# PCB.net
KiCad netlist of a schematic drawn in EAGLE
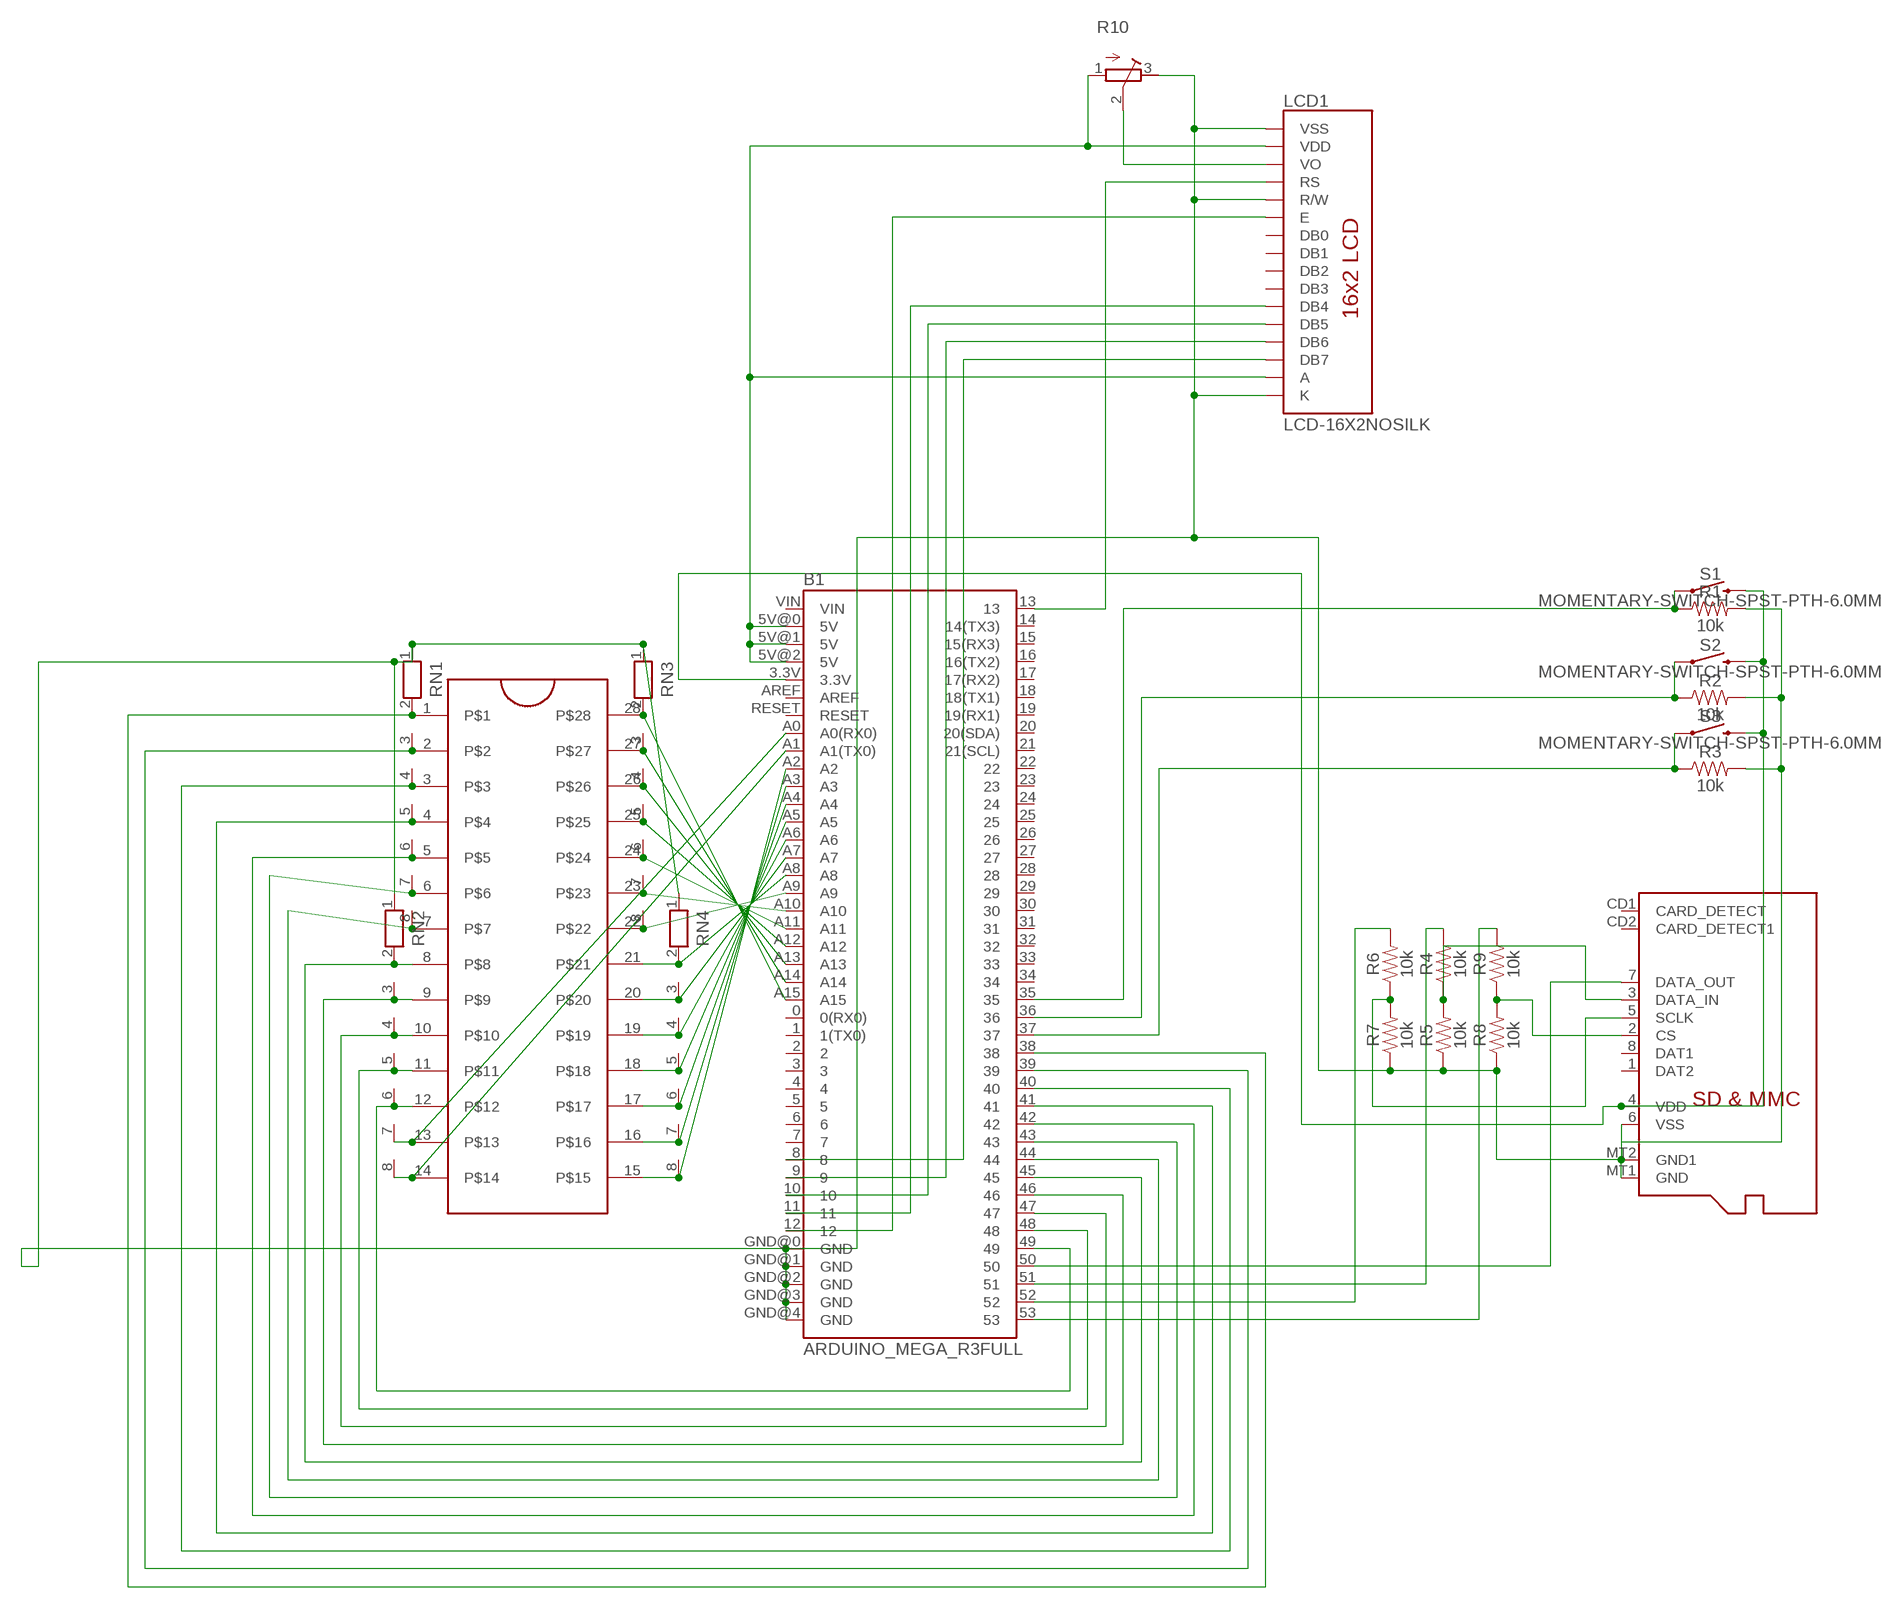
[diagram p0: schematic, sheet 1]

(export (version "E")
  (design (tool "Eeschema 10.0.6"))
  (components
    (comp (ref "B1")
      (value "ARDUINO_MEGA_R3FULL")
      (footprint "eagle-import:ARDUINO_MEGA")
      (libsource (lib "eagle-import") (part "ARDUINO_MEGA_R3FULL"))
    )
    (comp (ref "LCD1")
      (value "LCD-16X2NOSILK")
      (footprint "eagle-import:LCD-16X2_NOSILK")
      (libsource (lib "eagle-import") (part "LCD-16X2NOSILK"))
    )
    (comp (ref "R1")
      (value "10k")
      (footprint "eagle-import:AXIAL-0.3")
      (libsource (lib "eagle-import") (part "10KOHM-HORIZ-1/4W-5%"))
    )
    (comp (ref "R2")
      (value "10k")
      (footprint "eagle-import:AXIAL-0.3")
      (libsource (lib "eagle-import") (part "10KOHM-HORIZ-1/4W-5%"))
    )
    (comp (ref "R3")
      (value "10k")
      (footprint "eagle-import:AXIAL-0.3")
      (libsource (lib "eagle-import") (part "10KOHM-HORIZ-1/4W-5%"))
    )
    (comp (ref "R4")
      (value "10k")
      (footprint "eagle-import:AXIAL-0.3")
      (libsource (lib "eagle-import") (part "10KOHM-HORIZ-1/4W-5%"))
    )
    (comp (ref "R5")
      (value "10k")
      (footprint "eagle-import:AXIAL-0.3")
      (libsource (lib "eagle-import") (part "10KOHM-HORIZ-1/4W-5%"))
    )
    (comp (ref "R6")
      (value "10k")
      (footprint "eagle-import:AXIAL-0.3")
      (libsource (lib "eagle-import") (part "10KOHM-HORIZ-1/4W-5%"))
    )
    (comp (ref "R7")
      (value "10k")
      (footprint "eagle-import:AXIAL-0.3")
      (libsource (lib "eagle-import") (part "10KOHM-HORIZ-1/4W-5%"))
    )
    (comp (ref "R8")
      (value "10k")
      (footprint "eagle-import:AXIAL-0.3")
      (libsource (lib "eagle-import") (part "10KOHM-HORIZ-1/4W-5%"))
    )
    (comp (ref "R9")
      (value "10k")
      (footprint "eagle-import:AXIAL-0.3")
      (libsource (lib "eagle-import") (part "10KOHM-HORIZ-1/4W-5%"))
    )
    (comp (ref "R10")
      (value "R-TRIMM3339P")
      (footprint "eagle-import:RTRIM3339P")
      (libsource (lib "eagle-import") (part "R-TRIMM3339P"))
    )
    (comp (ref "RN1")
      (value "RN07")
      (footprint "eagle-import:RN-8")
      (libsource (lib "eagle-import") (part "RN07"))
    )
    (comp (ref "RN2")
      (value "RN07")
      (footprint "eagle-import:RN-8")
      (libsource (lib "eagle-import") (part "RN07"))
    )
    (comp (ref "RN3")
      (value "RN07")
      (footprint "eagle-import:RN-8")
      (libsource (lib "eagle-import") (part "RN07"))
    )
    (comp (ref "RN4")
      (value "RN07")
      (footprint "eagle-import:RN-8")
      (libsource (lib "eagle-import") (part "RN07"))
    )
    (comp (ref "S1")
      (value "MOMENTARY-SWITCH-SPST-PTH-6.0MM")
      (footprint "eagle-import:TACTILE_SWITCH_PTH_6.0MM")
      (libsource (lib "eagle-import") (part "MOMENTARY-SWITCH-SPST-PTH-6.0MM"))
    )
    (comp (ref "S2")
      (value "MOMENTARY-SWITCH-SPST-PTH-6.0MM")
      (footprint "eagle-import:TACTILE_SWITCH_PTH_6.0MM")
      (libsource (lib "eagle-import") (part "MOMENTARY-SWITCH-SPST-PTH-6.0MM"))
    )
    (comp (ref "S3")
      (value "MOMENTARY-SWITCH-SPST-PTH-6.0MM")
      (footprint "eagle-import:TACTILE_SWITCH_PTH_6.0MM")
      (libsource (lib "eagle-import") (part "MOMENTARY-SWITCH-SPST-PTH-6.0MM"))
    )
    (comp (ref "U$1")
      (value "MICROSD")
      (footprint "eagle-import:MICROSD")
      (libsource (lib "eagle-import") (part "MICROSD"))
    )
    (comp (ref "U$2")
      (value "ZIFSOCKET-28-3ZIFFSOCKET-28-3")
      (footprint "eagle-import:DIL28-3-ZIF_SOCKET")
      (libsource (lib "eagle-import") (part "ZIFSOCKET-28-3ZIFFSOCKET-28-3"))
    )
  )
  (nets
    (net (code "1") (name "Net-(B1-A0(RX0))") (class "Default")
      (node (ref "B1") (pin "A0") (pinfunction "A0(RX0)_A0") (pintype "bidirectional"))
      (node (ref "RN2") (pin "7") (pinfunction "7_7") (pintype "passive"))
      (node (ref "U$2") (pin "13") (pinfunction "P$13_13") (pintype "bidirectional"))
    )
    (net (code "2") (name "Net-(B1-A1(TX0))") (class "Default")
      (node (ref "B1") (pin "A1") (pinfunction "A1(TX0)_A1") (pintype "bidirectional"))
      (node (ref "RN2") (pin "8") (pinfunction "8_8") (pintype "passive"))
      (node (ref "U$2") (pin "14") (pinfunction "P$14_14") (pintype "bidirectional"))
    )
    (net (code "3") (name "Net-(LCD1-A)") (class "Default")
      (node (ref "B1") (pin "5V@0") (pinfunction "5V_5V@0") (pintype "bidirectional"))
      (node (ref "B1") (pin "5V@1") (pinfunction "5V_5V@1") (pintype "bidirectional"))
      (node (ref "B1") (pin "5V@2") (pinfunction "5V_5V@2") (pintype "bidirectional"))
      (node (ref "LCD1") (pin "15") (pinfunction "A_15") (pintype "power_in"))
      (node (ref "LCD1") (pin "2") (pinfunction "VDD_2") (pintype "power_in"))
      (node (ref "R10") (pin "1") (pinfunction "A_1") (pintype "passive"))
    )
    (net (code "4") (name "Net-(LCD1-DB4)") (class "Default")
      (node (ref "B1") (pin "11") (pinfunction "11_11") (pintype "bidirectional"))
      (node (ref "LCD1") (pin "11") (pinfunction "DB4_11") (pintype "bidirectional"))
    )
    (net (code "5") (name "Net-(LCD1-DB5)") (class "Default")
      (node (ref "B1") (pin "10") (pinfunction "10_10") (pintype "bidirectional"))
      (node (ref "LCD1") (pin "12") (pinfunction "DB5_12") (pintype "bidirectional"))
    )
    (net (code "6") (name "Net-(LCD1-DB6)") (class "Default")
      (node (ref "B1") (pin "9") (pinfunction "9_9") (pintype "bidirectional"))
      (node (ref "LCD1") (pin "13") (pinfunction "DB6_13") (pintype "bidirectional"))
    )
    (net (code "7") (name "Net-(LCD1-DB7)") (class "Default")
      (node (ref "B1") (pin "8") (pinfunction "8_8") (pintype "bidirectional"))
      (node (ref "LCD1") (pin "14") (pinfunction "DB7_14") (pintype "bidirectional"))
    )
    (net (code "8") (name "Net-(LCD1-E)") (class "Default")
      (node (ref "B1") (pin "12") (pinfunction "12_12") (pintype "bidirectional"))
      (node (ref "LCD1") (pin "6") (pinfunction "E_6") (pintype "input"))
    )
    (net (code "9") (name "Net-(LCD1-K)") (class "Default")
      (node (ref "B1") (pin "GND@0") (pinfunction "GND_GND@0") (pintype "bidirectional"))
      (node (ref "B1") (pin "GND@1") (pinfunction "GND_GND@1") (pintype "bidirectional"))
      (node (ref "B1") (pin "GND@2") (pinfunction "GND_GND@2") (pintype "bidirectional"))
      (node (ref "B1") (pin "GND@3") (pinfunction "GND_GND@3") (pintype "bidirectional"))
      (node (ref "B1") (pin "GND@4") (pinfunction "GND_GND@4") (pintype "bidirectional"))
      (node (ref "LCD1") (pin "1") (pinfunction "VSS_1") (pintype "power_in"))
      (node (ref "LCD1") (pin "16") (pinfunction "K_16") (pintype "power_in"))
      (node (ref "LCD1") (pin "5") (pinfunction "R/W_5") (pintype "input"))
      (node (ref "R1") (pin "P$2") (pinfunction "2_P$2") (pintype "passive"))
      (node (ref "R10") (pin "3") (pinfunction "E_3") (pintype "passive"))
      (node (ref "R2") (pin "P$2") (pinfunction "2_P$2") (pintype "passive"))
      (node (ref "R3") (pin "P$2") (pinfunction "2_P$2") (pintype "passive"))
      (node (ref "R5") (pin "P$1") (pinfunction "1_P$1") (pintype "passive"))
      (node (ref "R7") (pin "P$1") (pinfunction "1_P$1") (pintype "passive"))
      (node (ref "R8") (pin "P$1") (pinfunction "1_P$1") (pintype "passive"))
      (node (ref "RN1") (pin "1") (pinfunction "1_1") (pintype "passive"))
      (node (ref "RN2") (pin "1") (pinfunction "1_1") (pintype "passive"))
      (node (ref "RN3") (pin "1") (pinfunction "1_1") (pintype "passive"))
      (node (ref "RN4") (pin "1") (pinfunction "1_1") (pintype "passive"))
      (node (ref "U$1") (pin "6") (pinfunction "VSS_6") (pintype "power_in"))
      (node (ref "U$1") (pin "MT1") (pinfunction "GND_MT1") (pintype "power_in"))
      (node (ref "U$1") (pin "MT2") (pinfunction "GND1_MT2") (pintype "power_in"))
    )
    (net (code "10") (name "Net-(LCD1-RS)") (class "Default")
      (node (ref "B1") (pin "13") (pinfunction "13_13") (pintype "bidirectional"))
      (node (ref "LCD1") (pin "4") (pinfunction "RS_4") (pintype "input"))
    )
    (net (code "11") (name "Net-(LCD1-VO)") (class "Default")
      (node (ref "LCD1") (pin "3") (pinfunction "VO_3") (pintype "bidirectional"))
      (node (ref "R10") (pin "2") (pinfunction "S_2") (pintype "passive"))
    )
    (net (code "12") (name "Net-(R1-1)") (class "Default")
      (node (ref "B1") (pin "35") (pinfunction "35_35") (pintype "bidirectional"))
      (node (ref "R1") (pin "P$1") (pinfunction "1_P$1") (pintype "passive"))
      (node (ref "S1") (pin "1") (pinfunction "1_1") (pintype "passive"))
    )
    (net (code "13") (name "Net-(R2-1)") (class "Default")
      (node (ref "B1") (pin "36") (pinfunction "36_36") (pintype "bidirectional"))
      (node (ref "R2") (pin "P$1") (pinfunction "1_P$1") (pintype "passive"))
      (node (ref "S2") (pin "1") (pinfunction "1_1") (pintype "passive"))
    )
    (net (code "14") (name "Net-(R3-1)") (class "Default")
      (node (ref "B1") (pin "37") (pinfunction "37_37") (pintype "bidirectional"))
      (node (ref "R3") (pin "P$1") (pinfunction "1_P$1") (pintype "passive"))
      (node (ref "S3") (pin "1") (pinfunction "1_1") (pintype "passive"))
    )
    (net (code "15") (name "Net-(R4-1)") (class "Default")
      (node (ref "R4") (pin "P$1") (pinfunction "1_P$1") (pintype "passive"))
      (node (ref "R5") (pin "P$2") (pinfunction "2_P$2") (pintype "passive"))
      (node (ref "U$1") (pin "3") (pinfunction "DATA_IN_3") (pintype "input"))
    )
    (net (code "16") (name "Net-(R4-2)") (class "Default")
      (node (ref "B1") (pin "51") (pinfunction "51_51") (pintype "bidirectional"))
      (node (ref "R4") (pin "P$2") (pinfunction "2_P$2") (pintype "passive"))
    )
    (net (code "17") (name "Net-(R6-1)") (class "Default")
      (node (ref "R6") (pin "P$1") (pinfunction "1_P$1") (pintype "passive"))
      (node (ref "R7") (pin "P$2") (pinfunction "2_P$2") (pintype "passive"))
      (node (ref "U$1") (pin "5") (pinfunction "SCLK_5") (pintype "input"))
    )
    (net (code "18") (name "Net-(R6-2)") (class "Default")
      (node (ref "B1") (pin "52") (pinfunction "52_52") (pintype "bidirectional"))
      (node (ref "R6") (pin "P$2") (pinfunction "2_P$2") (pintype "passive"))
    )
    (net (code "19") (name "Net-(R8-2)") (class "Default")
      (node (ref "R8") (pin "P$2") (pinfunction "2_P$2") (pintype "passive"))
      (node (ref "R9") (pin "P$1") (pinfunction "1_P$1") (pintype "passive"))
      (node (ref "U$1") (pin "2") (pinfunction "CS_2") (pintype "input"))
    )
    (net (code "20") (name "Net-(R9-2)") (class "Default")
      (node (ref "B1") (pin "53") (pinfunction "53_53") (pintype "bidirectional"))
      (node (ref "R9") (pin "P$2") (pinfunction "2_P$2") (pintype "passive"))
    )
    (net (code "21") (name "Net-(S1-2)") (class "Default")
      (node (ref "B1") (pin "3.3V") (pinfunction "3.3V_3.3V") (pintype "bidirectional"))
      (node (ref "S1") (pin "3") (pinfunction "2_3") (pintype "passive"))
      (node (ref "S2") (pin "3") (pinfunction "2_3") (pintype "passive"))
      (node (ref "S3") (pin "3") (pinfunction "2_3") (pintype "passive"))
      (node (ref "U$1") (pin "4") (pinfunction "VDD_4") (pintype "power_in"))
    )
    (net (code "22") (name "Net-(U$1-DATA_OUT)") (class "Default")
      (node (ref "B1") (pin "50") (pinfunction "50_50") (pintype "bidirectional"))
      (node (ref "U$1") (pin "7") (pinfunction "DATA_OUT_7") (pintype "output"))
    )
    (net (code "23") (name "Net-(U$2-P$1)") (class "Default")
      (node (ref "B1") (pin "38") (pinfunction "38_38") (pintype "bidirectional"))
      (node (ref "RN1") (pin "2") (pinfunction "2_2") (pintype "passive"))
      (node (ref "U$2") (pin "1") (pinfunction "P$1_1") (pintype "bidirectional"))
    )
    (net (code "24") (name "Net-(U$2-P$2)") (class "Default")
      (node (ref "B1") (pin "39") (pinfunction "39_39") (pintype "bidirectional"))
      (node (ref "RN1") (pin "3") (pinfunction "3_3") (pintype "passive"))
      (node (ref "U$2") (pin "2") (pinfunction "P$2_2") (pintype "bidirectional"))
    )
    (net (code "25") (name "Net-(U$2-P$3)") (class "Default")
      (node (ref "B1") (pin "40") (pinfunction "40_40") (pintype "bidirectional"))
      (node (ref "RN1") (pin "4") (pinfunction "4_4") (pintype "passive"))
      (node (ref "U$2") (pin "3") (pinfunction "P$3_3") (pintype "bidirectional"))
    )
    (net (code "26") (name "Net-(U$2-P$4)") (class "Default")
      (node (ref "B1") (pin "41") (pinfunction "41_41") (pintype "bidirectional"))
      (node (ref "RN1") (pin "5") (pinfunction "5_5") (pintype "passive"))
      (node (ref "U$2") (pin "4") (pinfunction "P$4_4") (pintype "bidirectional"))
    )
    (net (code "27") (name "Net-(U$2-P$5)") (class "Default")
      (node (ref "B1") (pin "42") (pinfunction "42_42") (pintype "bidirectional"))
      (node (ref "RN1") (pin "6") (pinfunction "6_6") (pintype "passive"))
      (node (ref "U$2") (pin "5") (pinfunction "P$5_5") (pintype "bidirectional"))
    )
    (net (code "28") (name "Net-(U$2-P$6)") (class "Default")
      (node (ref "B1") (pin "43") (pinfunction "43_43") (pintype "bidirectional"))
      (node (ref "RN1") (pin "7") (pinfunction "7_7") (pintype "passive"))
      (node (ref "U$2") (pin "6") (pinfunction "P$6_6") (pintype "bidirectional"))
    )
    (net (code "29") (name "Net-(U$2-P$7)") (class "Default")
      (node (ref "B1") (pin "44") (pinfunction "44_44") (pintype "bidirectional"))
      (node (ref "RN1") (pin "8") (pinfunction "8_8") (pintype "passive"))
      (node (ref "U$2") (pin "7") (pinfunction "P$7_7") (pintype "bidirectional"))
    )
    (net (code "30") (name "Net-(U$2-P$8)") (class "Default")
      (node (ref "B1") (pin "45") (pinfunction "45_45") (pintype "bidirectional"))
      (node (ref "RN2") (pin "2") (pinfunction "2_2") (pintype "passive"))
      (node (ref "U$2") (pin "8") (pinfunction "P$8_8") (pintype "bidirectional"))
    )
    (net (code "31") (name "Net-(U$2-P$9)") (class "Default")
      (node (ref "B1") (pin "46") (pinfunction "46_46") (pintype "bidirectional"))
      (node (ref "RN2") (pin "3") (pinfunction "3_3") (pintype "passive"))
      (node (ref "U$2") (pin "9") (pinfunction "P$9_9") (pintype "bidirectional"))
    )
    (net (code "32") (name "Net-(U$2-P$10)") (class "Default")
      (node (ref "B1") (pin "47") (pinfunction "47_47") (pintype "bidirectional"))
      (node (ref "RN2") (pin "4") (pinfunction "4_4") (pintype "passive"))
      (node (ref "U$2") (pin "10") (pinfunction "P$10_10") (pintype "bidirectional"))
    )
    (net (code "33") (name "Net-(U$2-P$11)") (class "Default")
      (node (ref "B1") (pin "48") (pinfunction "48_48") (pintype "bidirectional"))
      (node (ref "RN2") (pin "5") (pinfunction "5_5") (pintype "passive"))
      (node (ref "U$2") (pin "11") (pinfunction "P$11_11") (pintype "bidirectional"))
    )
    (net (code "34") (name "Net-(U$2-P$12)") (class "Default")
      (node (ref "B1") (pin "49") (pinfunction "49_49") (pintype "bidirectional"))
      (node (ref "RN2") (pin "6") (pinfunction "6_6") (pintype "passive"))
      (node (ref "U$2") (pin "12") (pinfunction "P$12_12") (pintype "bidirectional"))
    )
    (net (code "35") (name "Net-(U$2-P$15)") (class "Default")
      (node (ref "B1") (pin "A2") (pinfunction "A2_A2") (pintype "bidirectional"))
      (node (ref "RN4") (pin "8") (pinfunction "8_8") (pintype "passive"))
      (node (ref "U$2") (pin "15") (pinfunction "P$15_15") (pintype "bidirectional"))
    )
    (net (code "36") (name "Net-(U$2-P$16)") (class "Default")
      (node (ref "B1") (pin "A3") (pinfunction "A3_A3") (pintype "bidirectional"))
      (node (ref "RN4") (pin "7") (pinfunction "7_7") (pintype "passive"))
      (node (ref "U$2") (pin "16") (pinfunction "P$16_16") (pintype "bidirectional"))
    )
    (net (code "37") (name "Net-(U$2-P$17)") (class "Default")
      (node (ref "B1") (pin "A4") (pinfunction "A4_A4") (pintype "bidirectional"))
      (node (ref "RN4") (pin "6") (pinfunction "6_6") (pintype "passive"))
      (node (ref "U$2") (pin "17") (pinfunction "P$17_17") (pintype "bidirectional"))
    )
    (net (code "38") (name "Net-(U$2-P$18)") (class "Default")
      (node (ref "B1") (pin "A5") (pinfunction "A5_A5") (pintype "bidirectional"))
      (node (ref "RN4") (pin "5") (pinfunction "5_5") (pintype "passive"))
      (node (ref "U$2") (pin "18") (pinfunction "P$18_18") (pintype "bidirectional"))
    )
    (net (code "39") (name "Net-(U$2-P$19)") (class "Default")
      (node (ref "B1") (pin "A6") (pinfunction "A6_A6") (pintype "bidirectional"))
      (node (ref "RN4") (pin "4") (pinfunction "4_4") (pintype "passive"))
      (node (ref "U$2") (pin "19") (pinfunction "P$19_19") (pintype "bidirectional"))
    )
    (net (code "40") (name "Net-(U$2-P$20)") (class "Default")
      (node (ref "B1") (pin "A7") (pinfunction "A7_A7") (pintype "bidirectional"))
      (node (ref "RN4") (pin "3") (pinfunction "3_3") (pintype "passive"))
      (node (ref "U$2") (pin "20") (pinfunction "P$20_20") (pintype "bidirectional"))
    )
    (net (code "41") (name "Net-(U$2-P$21)") (class "Default")
      (node (ref "B1") (pin "A8") (pinfunction "A8_A8") (pintype "bidirectional"))
      (node (ref "RN4") (pin "2") (pinfunction "2_2") (pintype "passive"))
      (node (ref "U$2") (pin "21") (pinfunction "P$21_21") (pintype "bidirectional"))
    )
    (net (code "42") (name "Net-(U$2-P$22)") (class "Default")
      (node (ref "B1") (pin "A9") (pinfunction "A9_A9") (pintype "bidirectional"))
      (node (ref "RN3") (pin "8") (pinfunction "8_8") (pintype "passive"))
      (node (ref "U$2") (pin "22") (pinfunction "P$22_22") (pintype "bidirectional"))
    )
    (net (code "43") (name "Net-(U$2-P$23)") (class "Default")
      (node (ref "B1") (pin "A10") (pinfunction "A10_A10") (pintype "bidirectional"))
      (node (ref "RN3") (pin "7") (pinfunction "7_7") (pintype "passive"))
      (node (ref "U$2") (pin "23") (pinfunction "P$23_23") (pintype "bidirectional"))
    )
    (net (code "44") (name "Net-(U$2-P$24)") (class "Default")
      (node (ref "B1") (pin "A11") (pinfunction "A11_A11") (pintype "bidirectional"))
      (node (ref "RN3") (pin "6") (pinfunction "6_6") (pintype "passive"))
      (node (ref "U$2") (pin "24") (pinfunction "P$24_24") (pintype "bidirectional"))
    )
    (net (code "45") (name "Net-(U$2-P$25)") (class "Default")
      (node (ref "B1") (pin "A12") (pinfunction "A12_A12") (pintype "bidirectional"))
      (node (ref "RN3") (pin "5") (pinfunction "5_5") (pintype "passive"))
      (node (ref "U$2") (pin "25") (pinfunction "P$25_25") (pintype "bidirectional"))
    )
    (net (code "46") (name "Net-(U$2-P$26)") (class "Default")
      (node (ref "B1") (pin "A13") (pinfunction "A13_A13") (pintype "bidirectional"))
      (node (ref "RN3") (pin "4") (pinfunction "4_4") (pintype "passive"))
      (node (ref "U$2") (pin "26") (pinfunction "P$26_26") (pintype "bidirectional"))
    )
    (net (code "47") (name "Net-(U$2-P$27)") (class "Default")
      (node (ref "B1") (pin "A14") (pinfunction "A14_A14") (pintype "bidirectional"))
      (node (ref "RN3") (pin "3") (pinfunction "3_3") (pintype "passive"))
      (node (ref "U$2") (pin "27") (pinfunction "P$27_27") (pintype "bidirectional"))
    )
    (net (code "48") (name "Net-(U$2-P$28)") (class "Default")
      (node (ref "B1") (pin "A15") (pinfunction "A15_A15") (pintype "bidirectional"))
      (node (ref "RN3") (pin "2") (pinfunction "2_2") (pintype "passive"))
      (node (ref "U$2") (pin "28") (pinfunction "P$28_28") (pintype "bidirectional"))
    )
    (net (code "49") (name "unconnected-(B1-0(RX0)-Pad0)") (class "Default")
      (node (ref "B1") (pin "0") (pinfunction "0(RX0)_0") (pintype "bidirectional"))
    )
    (net (code "50") (name "unconnected-(B1-1(TX0)-Pad1)") (class "Default")
      (node (ref "B1") (pin "1") (pinfunction "1(TX0)_1") (pintype "bidirectional"))
    )
    (net (code "51") (name "unconnected-(B1-14(TX3)-Pad14)") (class "Default")
      (node (ref "B1") (pin "14") (pinfunction "14(TX3)_14") (pintype "bidirectional"))
    )
    (net (code "52") (name "unconnected-(B1-15(RX3)-Pad15)") (class "Default")
      (node (ref "B1") (pin "15") (pinfunction "15(RX3)_15") (pintype "bidirectional"))
    )
    (net (code "53") (name "unconnected-(B1-16(TX2)-Pad16)") (class "Default")
      (node (ref "B1") (pin "16") (pinfunction "16(TX2)_16") (pintype "bidirectional"))
    )
    (net (code "54") (name "unconnected-(B1-17(RX2)-Pad17)") (class "Default")
      (node (ref "B1") (pin "17") (pinfunction "17(RX2)_17") (pintype "bidirectional"))
    )
    (net (code "55") (name "unconnected-(B1-18(TX1)-Pad18)") (class "Default")
      (node (ref "B1") (pin "18") (pinfunction "18(TX1)_18") (pintype "bidirectional"))
    )
    (net (code "56") (name "unconnected-(B1-19(RX1)-Pad19)") (class "Default")
      (node (ref "B1") (pin "19") (pinfunction "19(RX1)_19") (pintype "bidirectional"))
    )
    (net (code "57") (name "unconnected-(B1-20(SDA)-Pad20)") (class "Default")
      (node (ref "B1") (pin "20") (pinfunction "20(SDA)_20") (pintype "bidirectional"))
    )
    (net (code "58") (name "unconnected-(B1-21(SCL)-Pad21)") (class "Default")
      (node (ref "B1") (pin "21") (pinfunction "21(SCL)_21") (pintype "bidirectional"))
    )
    (net (code "59") (name "unconnected-(B1-Pad2)") (class "Default")
      (node (ref "B1") (pin "2") (pinfunction "2_2") (pintype "bidirectional"))
    )
    (net (code "60") (name "unconnected-(B1-Pad3)") (class "Default")
      (node (ref "B1") (pin "3") (pinfunction "3_3") (pintype "bidirectional"))
    )
    (net (code "61") (name "unconnected-(B1-Pad4)") (class "Default")
      (node (ref "B1") (pin "4") (pinfunction "4_4") (pintype "bidirectional"))
    )
    (net (code "62") (name "unconnected-(B1-Pad5)") (class "Default")
      (node (ref "B1") (pin "5") (pinfunction "5_5") (pintype "bidirectional"))
    )
    (net (code "63") (name "unconnected-(B1-Pad6)") (class "Default")
      (node (ref "B1") (pin "6") (pinfunction "6_6") (pintype "bidirectional"))
    )
    (net (code "64") (name "unconnected-(B1-Pad7)") (class "Default")
      (node (ref "B1") (pin "7") (pinfunction "7_7") (pintype "bidirectional"))
    )
    (net (code "65") (name "unconnected-(B1-Pad22)") (class "Default")
      (node (ref "B1") (pin "22") (pinfunction "22_22") (pintype "bidirectional"))
    )
    (net (code "66") (name "unconnected-(B1-Pad23)") (class "Default")
      (node (ref "B1") (pin "23") (pinfunction "23_23") (pintype "bidirectional"))
    )
    (net (code "67") (name "unconnected-(B1-Pad24)") (class "Default")
      (node (ref "B1") (pin "24") (pinfunction "24_24") (pintype "bidirectional"))
    )
    (net (code "68") (name "unconnected-(B1-Pad25)") (class "Default")
      (node (ref "B1") (pin "25") (pinfunction "25_25") (pintype "bidirectional"))
    )
    (net (code "69") (name "unconnected-(B1-Pad26)") (class "Default")
      (node (ref "B1") (pin "26") (pinfunction "26_26") (pintype "bidirectional"))
    )
    (net (code "70") (name "unconnected-(B1-Pad27)") (class "Default")
      (node (ref "B1") (pin "27") (pinfunction "27_27") (pintype "bidirectional"))
    )
    (net (code "71") (name "unconnected-(B1-Pad28)") (class "Default")
      (node (ref "B1") (pin "28") (pinfunction "28_28") (pintype "bidirectional"))
    )
    (net (code "72") (name "unconnected-(B1-Pad29)") (class "Default")
      (node (ref "B1") (pin "29") (pinfunction "29_29") (pintype "bidirectional"))
    )
    (net (code "73") (name "unconnected-(B1-Pad30)") (class "Default")
      (node (ref "B1") (pin "30") (pinfunction "30_30") (pintype "bidirectional"))
    )
    (net (code "74") (name "unconnected-(B1-Pad31)") (class "Default")
      (node (ref "B1") (pin "31") (pinfunction "31_31") (pintype "bidirectional"))
    )
    (net (code "75") (name "unconnected-(B1-Pad32)") (class "Default")
      (node (ref "B1") (pin "32") (pinfunction "32_32") (pintype "bidirectional"))
    )
    (net (code "76") (name "unconnected-(B1-Pad33)") (class "Default")
      (node (ref "B1") (pin "33") (pinfunction "33_33") (pintype "bidirectional"))
    )
    (net (code "77") (name "unconnected-(B1-Pad34)") (class "Default")
      (node (ref "B1") (pin "34") (pinfunction "34_34") (pintype "bidirectional"))
    )
    (net (code "78") (name "unconnected-(B1-PadAREF)") (class "Default")
      (node (ref "B1") (pin "AREF") (pinfunction "AREF_AREF") (pintype "bidirectional"))
    )
    (net (code "79") (name "unconnected-(B1-PadRESET)") (class "Default")
      (node (ref "B1") (pin "RESET") (pinfunction "RESET_RESET") (pintype "bidirectional"))
    )
    (net (code "80") (name "unconnected-(B1-PadVIN)") (class "Default")
      (node (ref "B1") (pin "VIN") (pinfunction "VIN_VIN") (pintype "bidirectional"))
    )
    (net (code "81") (name "unconnected-(LCD1-DB0-Pad7)") (class "Default")
      (node (ref "LCD1") (pin "7") (pinfunction "DB0_7") (pintype "bidirectional"))
    )
    (net (code "82") (name "unconnected-(LCD1-DB1-Pad8)") (class "Default")
      (node (ref "LCD1") (pin "8") (pinfunction "DB1_8") (pintype "bidirectional"))
    )
    (net (code "83") (name "unconnected-(LCD1-DB2-Pad9)") (class "Default")
      (node (ref "LCD1") (pin "9") (pinfunction "DB2_9") (pintype "bidirectional"))
    )
    (net (code "84") (name "unconnected-(LCD1-DB3-Pad10)") (class "Default")
      (node (ref "LCD1") (pin "10") (pinfunction "DB3_10") (pintype "bidirectional"))
    )
    (net (code "85") (name "unconnected-(U$1-CARD_DETECT-PadCD1)") (class "Default")
      (node (ref "U$1") (pin "CD1") (pinfunction "CARD_DETECT_CD1") (pintype "passive"))
    )
    (net (code "86") (name "unconnected-(U$1-CARD_DETECT1-PadCD2)") (class "Default")
      (node (ref "U$1") (pin "CD2") (pinfunction "CARD_DETECT1_CD2") (pintype "passive"))
    )
    (net (code "87") (name "unconnected-(U$1-DAT1-Pad8)") (class "Default")
      (node (ref "U$1") (pin "8") (pinfunction "DAT1_8") (pintype "bidirectional"))
    )
    (net (code "88") (name "unconnected-(U$1-DAT2-Pad1)") (class "Default")
      (node (ref "U$1") (pin "1") (pinfunction "DAT2_1") (pintype "bidirectional"))
    )
  )
)
